# BitsyExpander_v3_0_M4.net
KiCad netlist of a schematic drawn in EAGLE
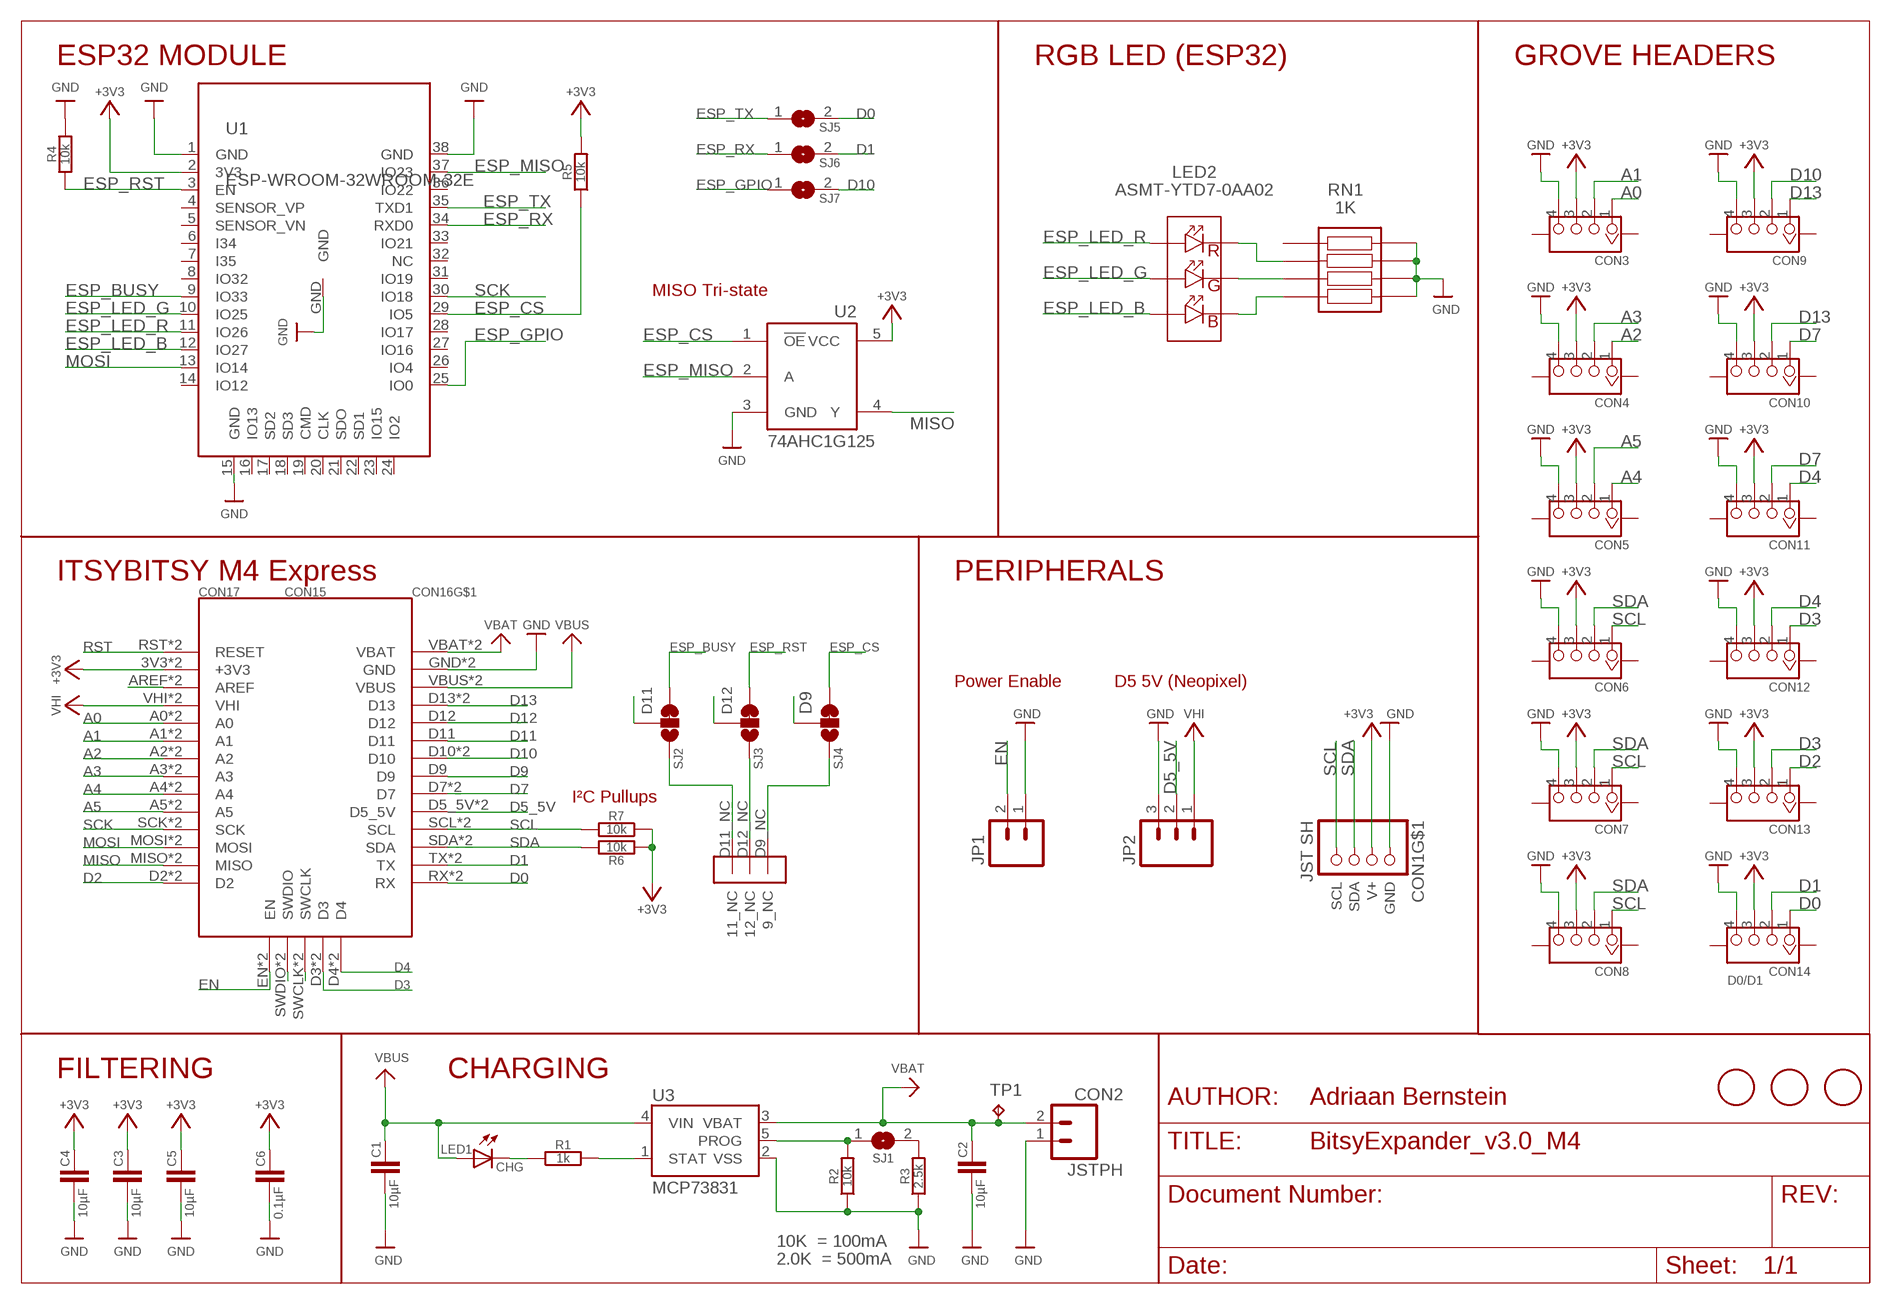
[diagram p0: schematic, sheet 1]

(export (version "E")
  (design (tool "Eeschema 10.0.6"))
  (components
    (comp (ref "C1")
      (value "10µF")
      (footprint "eagle-import:C0805")
      (libsource (lib "eagle-import") (part "C-EUC0805"))
    )
    (comp (ref "C2")
      (value "10µF")
      (footprint "eagle-import:C0805")
      (libsource (lib "eagle-import") (part "C-EUC0805"))
    )
    (comp (ref "C3")
      (value "10µF")
      (footprint "eagle-import:C0805")
      (libsource (lib "eagle-import") (part "C-EUC0805"))
    )
    (comp (ref "C4")
      (value "10µF")
      (footprint "eagle-import:C0805")
      (libsource (lib "eagle-import") (part "C-EUC0805"))
    )
    (comp (ref "C5")
      (value "10µF")
      (footprint "eagle-import:C0805")
      (libsource (lib "eagle-import") (part "C-EUC0805"))
    )
    (comp (ref "C6")
      (value "0.1µF")
      (footprint "eagle-import:C0805")
      (libsource (lib "eagle-import") (part "C-EUC0805"))
    )
    (comp (ref "CON1")
      (value "JST SH")
      (footprint "eagle-import:JST_SH4")
      (libsource (lib "eagle-import") (part "STEMMA_I2C_QT"))
    )
    (comp (ref "CON2")
      (value "JSTPH")
      (footprint "eagle-import:JST-2-SMD")
      (libsource (lib "eagle-import") (part "M02-JST-2MM-SMT"))
    )
    (comp (ref "CON3")
      (value "H4P-SMD-2.0")
      (footprint "eagle-import:HW4-PTH-2.0")
      (libsource (lib "eagle-import") (part "GROVE-CONNECTOR-4PINHW4-PTH-2.0"))
    )
    (comp (ref "CON4")
      (value "H4P-SMD-2.0")
      (footprint "eagle-import:HW4-PTH-2.0")
      (libsource (lib "eagle-import") (part "GROVE-CONNECTOR-4PINHW4-PTH-2.0"))
    )
    (comp (ref "CON5")
      (value "H4P-SMD-2.0")
      (footprint "eagle-import:HW4-PTH-2.0")
      (libsource (lib "eagle-import") (part "GROVE-CONNECTOR-4PINHW4-PTH-2.0"))
    )
    (comp (ref "CON6")
      (value "H4P-SMD-2.0")
      (footprint "eagle-import:HW4-PTH-2.0")
      (libsource (lib "eagle-import") (part "GROVE-CONNECTOR-4PINHW4-PTH-2.0"))
    )
    (comp (ref "CON7")
      (value "H4P-SMD-2.0")
      (footprint "eagle-import:HW4-PTH-2.0")
      (libsource (lib "eagle-import") (part "GROVE-CONNECTOR-4PINHW4-PTH-2.0"))
    )
    (comp (ref "CON8")
      (value "H4P-SMD-2.0")
      (footprint "eagle-import:HW4-PTH-2.0")
      (libsource (lib "eagle-import") (part "GROVE-CONNECTOR-4PINHW4-PTH-2.0"))
    )
    (comp (ref "CON9")
      (value "H4P-SMD-2.0")
      (footprint "eagle-import:HW4-PTH-2.0")
      (libsource (lib "eagle-import") (part "GROVE-CONNECTOR-4PINHW4-PTH-2.0"))
    )
    (comp (ref "CON10")
      (value "H4P-SMD-2.0")
      (footprint "eagle-import:HW4-PTH-2.0")
      (libsource (lib "eagle-import") (part "GROVE-CONNECTOR-4PINHW4-PTH-2.0"))
    )
    (comp (ref "CON11")
      (value "H4P-SMD-2.0")
      (footprint "eagle-import:HW4-PTH-2.0")
      (libsource (lib "eagle-import") (part "GROVE-CONNECTOR-4PINHW4-PTH-2.0"))
    )
    (comp (ref "CON12")
      (value "H4P-SMD-2.0")
      (footprint "eagle-import:HW4-PTH-2.0")
      (libsource (lib "eagle-import") (part "GROVE-CONNECTOR-4PINHW4-PTH-2.0"))
    )
    (comp (ref "CON13")
      (value "H4P-SMD-2.0")
      (footprint "eagle-import:HW4-PTH-2.0")
      (libsource (lib "eagle-import") (part "GROVE-CONNECTOR-4PINHW4-PTH-2.0"))
    )
    (comp (ref "CON14")
      (value "H4P-SMD-2.0")
      (footprint "eagle-import:HW4-PTH-2.0")
      (libsource (lib "eagle-import") (part "GROVE-CONNECTOR-4PINHW4-PTH-2.0"))
    )
    (comp (ref "CON15")
      (value "ITSYBITSY_EDGE_DEBUG")
      (footprint "eagle-import:ITSYBITSY_PTH_EDGE_DEBUG")
      (libsource (lib "eagle-import") (part "ITSYBITSY_EDGE_DEBUG"))
    )
    (comp (ref "CON16")
      (value "ITSYBITSY_EDGE_GND")
      (footprint "eagle-import:ITSYBITSY_SMD_EDGE_GND")
      (libsource (lib "eagle-import") (part "ITSYBITSY_EDGE_GND"))
    )
    (comp (ref "CON17")
      (value "ITSYBITSY_EDGE_PWR_M4EXPRESS")
      (footprint "eagle-import:ITSYBITSY_SMD_EDGE_PWR_M4EXPRESS")
      (libsource (lib "eagle-import") (part "ITSYBITSY_EDGE_PWR_M4EXPRESS"))
    )
    (comp (ref "FD1")
      (value "FIDUCIAL")
      (footprint "eagle-import:FIDUCIAL_1MM")
      (libsource (lib "eagle-import") (part "FIDUCIAL"))
    )
    (comp (ref "FD2")
      (value "FIDUCIAL")
      (footprint "eagle-import:FIDUCIAL_1MM")
      (libsource (lib "eagle-import") (part "FIDUCIAL"))
    )
    (comp (ref "FD3")
      (value "FIDUCIAL")
      (footprint "eagle-import:FIDUCIAL_1MM")
      (libsource (lib "eagle-import") (part "FIDUCIAL"))
    )
    (comp (ref "JP1")
      (value "M02PTH")
      (footprint "eagle-import:1X02")
      (libsource (lib "eagle-import") (part "M02PTH"))
    )
    (comp (ref "JP2")
      (value "M03PTH")
      (footprint "eagle-import:1X03")
      (libsource (lib "eagle-import") (part "M03PTH"))
    )
    (comp (ref "LED1")
      (value "CHG")
      (footprint "eagle-import:CHIP-LED0603")
      (libsource (lib "eagle-import") (part "LEDCHIP-LED0603"))
    )
    (comp (ref "LED2")
      (value "ASMT-YTD7-0AA02")
      (footprint "eagle-import:ASMTYTD70AA02")
      (fields (field (name "MOUSER_PART_NUMBER") "630-ASMT-YTD7-0AA02"))
      (libsource (lib "eagle-import") (part "ASMT-YTD7-0AA02"))
    )
    (comp (ref "R1")
      (value "1k")
      (footprint "eagle-import:R0603")
      (libsource (lib "eagle-import") (part "R-EU_R0603"))
    )
    (comp (ref "R2")
      (value "10k")
      (footprint "eagle-import:R0603")
      (libsource (lib "eagle-import") (part "R-EU_R0603"))
    )
    (comp (ref "R3")
      (value "2.5k")
      (footprint "eagle-import:R0603")
      (libsource (lib "eagle-import") (part "R-EU_R0603"))
    )
    (comp (ref "R4")
      (value "10k")
      (footprint "eagle-import:R0603")
      (libsource (lib "eagle-import") (part "R-EU_R0603"))
    )
    (comp (ref "R5")
      (value "10k")
      (footprint "eagle-import:R0603")
      (libsource (lib "eagle-import") (part "R-EU_R0603"))
    )
    (comp (ref "R6")
      (value "10k")
      (footprint "eagle-import:R0603")
      (libsource (lib "eagle-import") (part "R-EU_R0603"))
    )
    (comp (ref "R7")
      (value "10k")
      (footprint "eagle-import:R0603")
      (libsource (lib "eagle-import") (part "R-EU_R0603"))
    )
    (comp (ref "RN1")
      (value "1K")
      (footprint "eagle-import:CAY1647R0F4LF")
      (fields
        (field (name "MANUFACTURER_PART_NUMBER") "CAY16-221J4AS")
        (field (name "MOUSER_PART_NUMBER") "652-CAY16-221J4AS")
      )
      (libsource (lib "eagle-import") (part "CAY16-221J4AS"))
    )
    (comp (ref "SJ1") (value "SJ") (footprint "eagle-import:SJ") (libsource (lib "eagle-import") (part "SJ")))
    (comp (ref "SJ5") (value "SJ") (footprint "eagle-import:SJ") (libsource (lib "eagle-import") (part "SJ")))
    (comp (ref "SJ6") (value "SJ") (footprint "eagle-import:SJ") (libsource (lib "eagle-import") (part "SJ")))
    (comp (ref "SJ7") (value "SJ") (footprint "eagle-import:SJ") (libsource (lib "eagle-import") (part "SJ")))
    (comp (ref "SJ_D11")
      (value "SJ2")
      (footprint "eagle-import:SJ_2WAY_CLOSED")
      (libsource (lib "eagle-import") (part "SJ_2WAY_CLOSED"))
    )
    (comp (ref "SJ_D12")
      (value "SJ3")
      (footprint "eagle-import:SJ_2WAY_CLOSED")
      (libsource (lib "eagle-import") (part "SJ_2WAY_CLOSED"))
    )
    (comp (ref "SJ_D13")
      (value "SJ4")
      (footprint "eagle-import:SJ_2WAY_CLOSED")
      (libsource (lib "eagle-import") (part "SJ_2WAY_CLOSED"))
    )
    (comp (ref "TP1")
      (value "TPB1,27")
      (footprint "eagle-import:B1,27")
      (libsource (lib "eagle-import") (part "TPB1,27"))
    )
    (comp (ref "U1")
      (value "ESP-WROOM-32WROOM-32E")
      (footprint "eagle-import:ESP-WROOM-32E")
      (libsource (lib "eagle-import") (part "ESP-WROOM-32WROOM-32E"))
    )
    (comp (ref "U2")
      (value "74AHC1G125")
      (footprint "eagle-import:SOT23-5L")
      (libsource (lib "eagle-import") (part "74AHC1G125"))
    )
    (comp (ref "U3")
      (value "MCP73831")
      (footprint "eagle-import:SOT23-5")
      (libsource (lib "eagle-import") (part "MCP73831"))
    )
  )
  (nets
    (net (code "1") (name "+3V3") (class "Default")
      (node (ref "C3") (pin "1") (pinfunction "1_1") (pintype "passive"))
      (node (ref "C4") (pin "1") (pinfunction "1_1") (pintype "passive"))
      (node (ref "C5") (pin "1") (pinfunction "1_1") (pintype "passive"))
      (node (ref "C6") (pin "1") (pinfunction "1_1") (pintype "passive"))
      (node (ref "CON1") (pin "2") (pinfunction "V+_2") (pintype "passive"))
      (node (ref "CON10") (pin "3") (pinfunction "3_3") (pintype "bidirectional"))
      (node (ref "CON11") (pin "3") (pinfunction "3_3") (pintype "bidirectional"))
      (node (ref "CON12") (pin "3") (pinfunction "3_3") (pintype "bidirectional"))
      (node (ref "CON13") (pin "3") (pinfunction "3_3") (pintype "bidirectional"))
      (node (ref "CON14") (pin "3") (pinfunction "3_3") (pintype "bidirectional"))
      (node (ref "CON17") (pin "3V3") (pinfunction "+3V3_3V3") (pintype "bidirectional"))
      (node (ref "CON17") (pin "3V3_2") (pinfunction "+3V3_3V3_2") (pintype "bidirectional"))
      (node (ref "CON3") (pin "3") (pinfunction "3_3") (pintype "bidirectional"))
      (node (ref "CON4") (pin "3") (pinfunction "3_3") (pintype "bidirectional"))
      (node (ref "CON5") (pin "3") (pinfunction "3_3") (pintype "bidirectional"))
      (node (ref "CON6") (pin "3") (pinfunction "3_3") (pintype "bidirectional"))
      (node (ref "CON7") (pin "3") (pinfunction "3_3") (pintype "bidirectional"))
      (node (ref "CON8") (pin "3") (pinfunction "3_3") (pintype "bidirectional"))
      (node (ref "CON9") (pin "3") (pinfunction "3_3") (pintype "bidirectional"))
      (node (ref "R5") (pin "2") (pinfunction "2_2") (pintype "passive"))
      (node (ref "R6") (pin "1") (pinfunction "1_1") (pintype "passive"))
      (node (ref "R7") (pin "1") (pinfunction "1_1") (pintype "passive"))
      (node (ref "U1") (pin "2") (pinfunction "3V3_2") (pintype "bidirectional"))
      (node (ref "U2") (pin "5") (pinfunction "VCC_5") (pintype "power_in"))
    )
    (net (code "2") (name "/A0") (class "Default")
      (node (ref "CON17") (pin "A0") (pinfunction "A0_A0") (pintype "bidirectional"))
      (node (ref "CON17") (pin "A0_2") (pinfunction "A0_A0_2") (pintype "bidirectional"))
      (node (ref "CON3") (pin "1") (pinfunction "1_1") (pintype "bidirectional"))
    )
    (net (code "3") (name "/A1") (class "Default")
      (node (ref "CON17") (pin "A1") (pinfunction "A1_A1") (pintype "bidirectional"))
      (node (ref "CON17") (pin "A1_2") (pinfunction "A1_A1_2") (pintype "bidirectional"))
      (node (ref "CON3") (pin "2") (pinfunction "2_2") (pintype "bidirectional"))
    )
    (net (code "4") (name "/A2") (class "Default")
      (node (ref "CON17") (pin "A2") (pinfunction "A2_A2") (pintype "bidirectional"))
      (node (ref "CON17") (pin "A2_2") (pinfunction "A2_A2_2") (pintype "bidirectional"))
      (node (ref "CON4") (pin "1") (pinfunction "1_1") (pintype "bidirectional"))
    )
    (net (code "5") (name "/A3") (class "Default")
      (node (ref "CON17") (pin "A3") (pinfunction "A3_A3") (pintype "bidirectional"))
      (node (ref "CON17") (pin "A3_2") (pinfunction "A3_A3_2") (pintype "bidirectional"))
      (node (ref "CON4") (pin "2") (pinfunction "2_2") (pintype "bidirectional"))
    )
    (net (code "6") (name "/A4") (class "Default")
      (node (ref "CON17") (pin "A4") (pinfunction "A4_A4") (pintype "bidirectional"))
      (node (ref "CON17") (pin "A4_2") (pinfunction "A4_A4_2") (pintype "bidirectional"))
      (node (ref "CON5") (pin "1") (pinfunction "1_1") (pintype "bidirectional"))
    )
    (net (code "7") (name "/A5") (class "Default")
      (node (ref "CON17") (pin "A5") (pinfunction "A5_A5") (pintype "bidirectional"))
      (node (ref "CON17") (pin "A5_2") (pinfunction "A5_A5_2") (pintype "bidirectional"))
      (node (ref "CON5") (pin "2") (pinfunction "2_2") (pintype "bidirectional"))
    )
    (net (code "8") (name "/D0") (class "Default")
      (node (ref "CON14") (pin "1") (pinfunction "1_1") (pintype "bidirectional"))
      (node (ref "CON15") (pin "RX") (pinfunction "RX_RX") (pintype "bidirectional"))
      (node (ref "CON15") (pin "RX_2") (pinfunction "RX_RX_2") (pintype "bidirectional"))
      (node (ref "SJ5") (pin "2") (pinfunction "2_2") (pintype "passive"))
    )
    (net (code "9") (name "/D1") (class "Default")
      (node (ref "CON14") (pin "2") (pinfunction "2_2") (pintype "bidirectional"))
      (node (ref "CON16") (pin "TX") (pinfunction "TX_TX") (pintype "bidirectional"))
      (node (ref "CON16") (pin "TX_2") (pinfunction "TX_TX_2") (pintype "bidirectional"))
      (node (ref "SJ6") (pin "2") (pinfunction "2_2") (pintype "passive"))
    )
    (net (code "10") (name "/D2") (class "Default")
      (node (ref "CON13") (pin "1") (pinfunction "1_1") (pintype "bidirectional"))
      (node (ref "CON15") (pin "D2") (pinfunction "D2_D2") (pintype "bidirectional"))
      (node (ref "CON15") (pin "D2_2") (pinfunction "D2_D2_2") (pintype "bidirectional"))
    )
    (net (code "11") (name "/D3") (class "Default")
      (node (ref "CON12") (pin "1") (pinfunction "1_1") (pintype "bidirectional"))
      (node (ref "CON13") (pin "2") (pinfunction "2_2") (pintype "bidirectional"))
      (node (ref "CON15") (pin "D3") (pinfunction "D3_D3") (pintype "bidirectional"))
      (node (ref "CON15") (pin "D3_2") (pinfunction "D3_D3_2") (pintype "bidirectional"))
    )
    (net (code "12") (name "/D4") (class "Default")
      (node (ref "CON11") (pin "1") (pinfunction "1_1") (pintype "bidirectional"))
      (node (ref "CON12") (pin "2") (pinfunction "2_2") (pintype "bidirectional"))
      (node (ref "CON15") (pin "D4") (pinfunction "D4_D4") (pintype "bidirectional"))
      (node (ref "CON15") (pin "D4_2") (pinfunction "D4_D4_2") (pintype "bidirectional"))
    )
    (net (code "13") (name "/D5_5V") (class "Default")
      (node (ref "CON16") (pin "D5_5V") (pinfunction "D5_5V_D5_5V") (pintype "bidirectional"))
      (node (ref "CON16") (pin "D5_5V_2") (pinfunction "D5_5V_D5_5V_2") (pintype "bidirectional"))
      (node (ref "JP2") (pin "2") (pinfunction "2_2") (pintype "passive"))
    )
    (net (code "14") (name "/D7") (class "Default")
      (node (ref "CON10") (pin "1") (pinfunction "1_1") (pintype "bidirectional"))
      (node (ref "CON11") (pin "2") (pinfunction "2_2") (pintype "bidirectional"))
      (node (ref "CON16") (pin "D7") (pinfunction "D7_D7") (pintype "bidirectional"))
      (node (ref "CON16") (pin "D7_2") (pinfunction "D7_D7_2") (pintype "bidirectional"))
    )
    (net (code "15") (name "/D9") (class "Default")
      (node (ref "CON16") (pin "D9") (pinfunction "D9_D9") (pintype "bidirectional"))
      (node (ref "SJ_D13") (pin "2") (pinfunction "2_2") (pintype "passive"))
    )
    (net (code "16") (name "/D10") (class "Default")
      (node (ref "CON16") (pin "D10") (pinfunction "D10_D10") (pintype "bidirectional"))
      (node (ref "CON16") (pin "D10_2") (pinfunction "D10_D10_2") (pintype "bidirectional"))
      (node (ref "CON9") (pin "2") (pinfunction "2_2") (pintype "bidirectional"))
      (node (ref "SJ7") (pin "2") (pinfunction "2_2") (pintype "passive"))
    )
    (net (code "17") (name "/D11") (class "Default")
      (node (ref "CON16") (pin "D11") (pinfunction "D11_D11") (pintype "bidirectional"))
      (node (ref "SJ_D11") (pin "2") (pinfunction "2_2") (pintype "passive"))
    )
    (net (code "18") (name "/D12") (class "Default")
      (node (ref "CON16") (pin "D12") (pinfunction "D12_D12") (pintype "bidirectional"))
      (node (ref "SJ_D12") (pin "2") (pinfunction "2_2") (pintype "passive"))
    )
    (net (code "19") (name "/D13") (class "Default")
      (node (ref "CON10") (pin "2") (pinfunction "2_2") (pintype "bidirectional"))
      (node (ref "CON16") (pin "D13") (pinfunction "D13_D13") (pintype "bidirectional"))
      (node (ref "CON16") (pin "D13_2") (pinfunction "D13_D13_2") (pintype "bidirectional"))
      (node (ref "CON9") (pin "1") (pinfunction "1_1") (pintype "bidirectional"))
    )
    (net (code "20") (name "/EN") (class "Default")
      (node (ref "CON15") (pin "EN") (pinfunction "EN_EN") (pintype "bidirectional"))
      (node (ref "CON15") (pin "EN_2") (pinfunction "EN_EN_2") (pintype "bidirectional"))
      (node (ref "JP1") (pin "2") (pinfunction "2_2") (pintype "passive"))
    )
    (net (code "21") (name "/ESP_BUSY") (class "Default")
      (node (ref "SJ_D11") (pin "1") (pinfunction "1_1") (pintype "passive"))
      (node (ref "U1") (pin "9") (pinfunction "IO33_9") (pintype "bidirectional"))
    )
    (net (code "22") (name "/ESP_CS") (class "Default")
      (node (ref "R5") (pin "1") (pinfunction "1_1") (pintype "passive"))
      (node (ref "SJ_D13") (pin "1") (pinfunction "1_1") (pintype "passive"))
      (node (ref "U1") (pin "29") (pinfunction "IO5_29") (pintype "bidirectional"))
      (node (ref "U2") (pin "1") (pinfunction "~{OE}_1") (pintype "input"))
    )
    (net (code "23") (name "/ESP_GPIO") (class "Default")
      (node (ref "SJ7") (pin "1") (pinfunction "1_1") (pintype "passive"))
      (node (ref "U1") (pin "25") (pinfunction "IO0_25") (pintype "bidirectional"))
    )
    (net (code "24") (name "/ESP_LED_B") (class "Default")
      (node (ref "LED2") (pin "6") (pinfunction "A_BLUE_6") (pintype "bidirectional"))
      (node (ref "U1") (pin "12") (pinfunction "IO27_12") (pintype "bidirectional"))
    )
    (net (code "25") (name "/ESP_LED_G") (class "Default")
      (node (ref "LED2") (pin "5") (pinfunction "A_GREEN_5") (pintype "bidirectional"))
      (node (ref "U1") (pin "10") (pinfunction "IO25_10") (pintype "bidirectional"))
    )
    (net (code "26") (name "/ESP_LED_R") (class "Default")
      (node (ref "LED2") (pin "4") (pinfunction "A_RED_4") (pintype "bidirectional"))
      (node (ref "U1") (pin "11") (pinfunction "IO26_11") (pintype "bidirectional"))
    )
    (net (code "27") (name "/ESP_MISO") (class "Default")
      (node (ref "U1") (pin "37") (pinfunction "IO23_37") (pintype "bidirectional"))
      (node (ref "U2") (pin "2") (pinfunction "A_2") (pintype "input"))
    )
    (net (code "28") (name "/ESP_RST") (class "Default")
      (node (ref "R4") (pin "1") (pinfunction "1_1") (pintype "passive"))
      (node (ref "SJ_D12") (pin "1") (pinfunction "1_1") (pintype "passive"))
      (node (ref "U1") (pin "3") (pinfunction "EN_3") (pintype "bidirectional"))
    )
    (net (code "29") (name "/ESP_RX") (class "Default")
      (node (ref "SJ6") (pin "1") (pinfunction "1_1") (pintype "passive"))
      (node (ref "U1") (pin "34") (pinfunction "RXD0_34") (pintype "bidirectional"))
    )
    (net (code "30") (name "/ESP_TX") (class "Default")
      (node (ref "SJ5") (pin "1") (pinfunction "1_1") (pintype "passive"))
      (node (ref "U1") (pin "35") (pinfunction "TXD1_35") (pintype "bidirectional"))
    )
    (net (code "31") (name "/MISO") (class "Default")
      (node (ref "CON17") (pin "MISO") (pinfunction "MISO_MISO") (pintype "bidirectional"))
      (node (ref "CON17") (pin "MISO_2") (pinfunction "MISO_MISO_2") (pintype "bidirectional"))
      (node (ref "U2") (pin "4") (pinfunction "Y_4") (pintype "output"))
    )
    (net (code "32") (name "/MOSI") (class "Default")
      (node (ref "CON17") (pin "MOSI") (pinfunction "MOSI_MOSI") (pintype "bidirectional"))
      (node (ref "CON17") (pin "MOSI_2") (pinfunction "MOSI_MOSI_2") (pintype "bidirectional"))
      (node (ref "U1") (pin "13") (pinfunction "IO14_13") (pintype "bidirectional"))
    )
    (net (code "33") (name "/RST") (class "Default")
      (node (ref "CON17") (pin "RST") (pinfunction "RESET_RST") (pintype "bidirectional"))
      (node (ref "CON17") (pin "RST_2") (pinfunction "RESET_RST_2") (pintype "bidirectional"))
    )
    (net (code "34") (name "/SCK") (class "Default")
      (node (ref "CON17") (pin "SCK") (pinfunction "SCK_SCK") (pintype "bidirectional"))
      (node (ref "CON17") (pin "SCK_2") (pinfunction "SCK_SCK_2") (pintype "bidirectional"))
      (node (ref "U1") (pin "30") (pinfunction "IO18_30") (pintype "bidirectional"))
    )
    (net (code "35") (name "/SCL") (class "Default")
      (node (ref "CON1") (pin "4") (pinfunction "SCL_4") (pintype "passive"))
      (node (ref "CON16") (pin "SCL") (pinfunction "SCL_SCL") (pintype "bidirectional"))
      (node (ref "CON16") (pin "SCL_2") (pinfunction "SCL_SCL_2") (pintype "bidirectional"))
      (node (ref "CON6") (pin "1") (pinfunction "1_1") (pintype "bidirectional"))
      (node (ref "CON7") (pin "1") (pinfunction "1_1") (pintype "bidirectional"))
      (node (ref "CON8") (pin "1") (pinfunction "1_1") (pintype "bidirectional"))
      (node (ref "R7") (pin "2") (pinfunction "2_2") (pintype "passive"))
    )
    (net (code "36") (name "/SDA") (class "Default")
      (node (ref "CON1") (pin "3") (pinfunction "SDA_3") (pintype "passive"))
      (node (ref "CON16") (pin "SDA") (pinfunction "SDA_SDA") (pintype "bidirectional"))
      (node (ref "CON16") (pin "SDA_2") (pinfunction "SDA_SDA_2") (pintype "bidirectional"))
      (node (ref "CON6") (pin "2") (pinfunction "2_2") (pintype "bidirectional"))
      (node (ref "CON7") (pin "2") (pinfunction "2_2") (pintype "bidirectional"))
      (node (ref "CON8") (pin "2") (pinfunction "2_2") (pintype "bidirectional"))
      (node (ref "R6") (pin "2") (pinfunction "2_2") (pintype "passive"))
    )
    (net (code "37") (name "GND") (class "Default")
      (node (ref "C1") (pin "2") (pinfunction "2_2") (pintype "passive"))
      (node (ref "C2") (pin "2") (pinfunction "2_2") (pintype "passive"))
      (node (ref "C3") (pin "2") (pinfunction "2_2") (pintype "passive"))
      (node (ref "C4") (pin "2") (pinfunction "2_2") (pintype "passive"))
      (node (ref "C5") (pin "2") (pinfunction "2_2") (pintype "passive"))
      (node (ref "C6") (pin "2") (pinfunction "2_2") (pintype "passive"))
      (node (ref "CON1") (pin "1") (pinfunction "GND_1") (pintype "passive"))
      (node (ref "CON10") (pin "4") (pinfunction "4_4") (pintype "bidirectional"))
      (node (ref "CON11") (pin "4") (pinfunction "4_4") (pintype "bidirectional"))
      (node (ref "CON12") (pin "4") (pinfunction "4_4") (pintype "bidirectional"))
      (node (ref "CON13") (pin "4") (pinfunction "4_4") (pintype "bidirectional"))
      (node (ref "CON14") (pin "4") (pinfunction "4_4") (pintype "bidirectional"))
      (node (ref "CON16") (pin "GND") (pinfunction "GND_GND") (pintype "bidirectional"))
      (node (ref "CON16") (pin "GND_2") (pinfunction "GND_GND_2") (pintype "bidirectional"))
      (node (ref "CON2") (pin "1") (pinfunction "1_1") (pintype "passive"))
      (node (ref "CON3") (pin "4") (pinfunction "4_4") (pintype "bidirectional"))
      (node (ref "CON4") (pin "4") (pinfunction "4_4") (pintype "bidirectional"))
      (node (ref "CON5") (pin "4") (pinfunction "4_4") (pintype "bidirectional"))
      (node (ref "CON6") (pin "4") (pinfunction "4_4") (pintype "bidirectional"))
      (node (ref "CON7") (pin "4") (pinfunction "4_4") (pintype "bidirectional"))
      (node (ref "CON8") (pin "4") (pinfunction "4_4") (pintype "bidirectional"))
      (node (ref "CON9") (pin "4") (pinfunction "4_4") (pintype "bidirectional"))
      (node (ref "JP1") (pin "1") (pinfunction "1_1") (pintype "passive"))
      (node (ref "JP2") (pin "3") (pinfunction "3_3") (pintype "passive"))
      (node (ref "R2") (pin "1") (pinfunction "1_1") (pintype "passive"))
      (node (ref "R3") (pin "1") (pinfunction "1_1") (pintype "passive"))
      (node (ref "R4") (pin "2") (pinfunction "2_2") (pintype "passive"))
      (node (ref "RN1") (pin "5") (pinfunction "R4_2_5") (pintype "bidirectional"))
      (node (ref "RN1") (pin "6") (pinfunction "R3_2_6") (pintype "bidirectional"))
      (node (ref "RN1") (pin "7") (pinfunction "R2_2_7") (pintype "bidirectional"))
      (node (ref "RN1") (pin "8") (pinfunction "R1_2_8") (pintype "bidirectional"))
      (node (ref "U1") (pin "1") (pinfunction "GND_1") (pintype "bidirectional"))
      (node (ref "U1") (pin "15") (pinfunction "GND_15") (pintype "bidirectional"))
      (node (ref "U1") (pin "38") (pinfunction "GND_38") (pintype "bidirectional"))
      (node (ref "U1") (pin "GND") (pinfunction "GND_GND") (pintype "bidirectional"))
      (node (ref "U2") (pin "3") (pinfunction "GND_3") (pintype "power_in"))
      (node (ref "U3") (pin "2") (pinfunction "VSS_2") (pintype "power_in"))
    )
    (net (code "38") (name "Net-(CON15-PadSWCLK)") (class "Default")
      (node (ref "CON15") (pin "SWCLK") (pinfunction "SWCLK_SWCLK") (pintype "bidirectional"))
      (node (ref "CON15") (pin "SWCLK_2") (pinfunction "SWCLK_SWCLK_2") (pintype "bidirectional"))
    )
    (net (code "39") (name "Net-(CON15-PadSWDIO)") (class "Default")
      (node (ref "CON15") (pin "SWDIO") (pinfunction "SWDIO_SWDIO") (pintype "bidirectional"))
      (node (ref "CON15") (pin "SWDIO_2") (pinfunction "SWDIO_SWDIO_2") (pintype "bidirectional"))
    )
    (net (code "40") (name "Net-(CON16B-9_NC)") (class "Default")
      (node (ref "CON16") (pin "D9_NC") (pinfunction "9_NC_D9_NC") (pintype "bidirectional"))
      (node (ref "SJ_D13") (pin "3") (pinfunction "3_3") (pintype "passive"))
    )
    (net (code "41") (name "Net-(CON16B-11_NC)") (class "Default")
      (node (ref "CON16") (pin "D11_NC") (pinfunction "11_NC_D11_NC") (pintype "bidirectional"))
      (node (ref "SJ_D11") (pin "3") (pinfunction "3_3") (pintype "passive"))
    )
    (net (code "42") (name "Net-(CON16B-12_NC)") (class "Default")
      (node (ref "CON16") (pin "D12_NC") (pinfunction "12_NC_D12_NC") (pintype "bidirectional"))
      (node (ref "SJ_D12") (pin "3") (pinfunction "3_3") (pintype "passive"))
    )
    (net (code "43") (name "Net-(CON17-AREF-PadAREF_2)") (class "Default")
      (node (ref "CON17") (pin "AREF") (pinfunction "AREF_AREF") (pintype "bidirectional"))
      (node (ref "CON17") (pin "AREF_2") (pinfunction "AREF_AREF_2") (pintype "bidirectional"))
    )
    (net (code "44") (name "Net-(LED1-PadC)") (class "Default")
      (node (ref "LED1") (pin "C") (pinfunction "C_C") (pintype "passive"))
      (node (ref "R1") (pin "1") (pinfunction "1_1") (pintype "passive"))
    )
    (net (code "45") (name "Net-(LED2-K_BLUE)") (class "Default")
      (node (ref "LED2") (pin "1") (pinfunction "K_BLUE_1") (pintype "bidirectional"))
      (node (ref "RN1") (pin "4") (pinfunction "R4_1_4") (pintype "bidirectional"))
    )
    (net (code "46") (name "Net-(LED2-K_GREEN)") (class "Default")
      (node (ref "LED2") (pin "2") (pinfunction "K_GREEN_2") (pintype "bidirectional"))
      (node (ref "RN1") (pin "3") (pinfunction "R3_1_3") (pintype "bidirectional"))
    )
    (net (code "47") (name "Net-(LED2-K_RED)") (class "Default")
      (node (ref "LED2") (pin "3") (pinfunction "K_RED_3") (pintype "bidirectional"))
      (node (ref "RN1") (pin "2") (pinfunction "R2_1_2") (pintype "bidirectional"))
    )
    (net (code "48") (name "Net-(R3-Pad2)") (class "Default")
      (node (ref "R3") (pin "2") (pinfunction "2_2") (pintype "passive"))
      (node (ref "SJ1") (pin "2") (pinfunction "2_2") (pintype "passive"))
    )
    (net (code "49") (name "Net-(U3-PROG)") (class "Default")
      (node (ref "R2") (pin "2") (pinfunction "2_2") (pintype "passive"))
      (node (ref "SJ1") (pin "1") (pinfunction "1_1") (pintype "passive"))
      (node (ref "U3") (pin "5") (pinfunction "PROG_5") (pintype "input"))
    )
    (net (code "50") (name "Net-(U3-STAT)") (class "Default")
      (node (ref "R1") (pin "2") (pinfunction "2_2") (pintype "passive"))
      (node (ref "U3") (pin "1") (pinfunction "STAT_1") (pintype "output"))
    )
    (net (code "51") (name "VBAT") (class "Default")
      (node (ref "C2") (pin "1") (pinfunction "1_1") (pintype "passive"))
      (node (ref "CON16") (pin "VBAT") (pinfunction "VBAT_VBAT") (pintype "bidirectional"))
      (node (ref "CON16") (pin "VBAT_2") (pinfunction "VBAT_VBAT_2") (pintype "bidirectional"))
      (node (ref "CON2") (pin "2") (pinfunction "2_2") (pintype "passive"))
      (node (ref "TP1") (pin "TP") (pinfunction "TP_TP") (pintype "input"))
      (node (ref "U3") (pin "3") (pinfunction "VBAT_3") (pintype "power_in"))
    )
    (net (code "52") (name "VBUS") (class "Default")
      (node (ref "C1") (pin "1") (pinfunction "1_1") (pintype "passive"))
      (node (ref "CON16") (pin "VBUS") (pinfunction "VBUS_VBUS") (pintype "bidirectional"))
      (node (ref "CON16") (pin "VBUS_2") (pinfunction "VBUS_VBUS_2") (pintype "bidirectional"))
      (node (ref "LED1") (pin "A") (pinfunction "A_A") (pintype "passive"))
      (node (ref "U3") (pin "4") (pinfunction "VIN_4") (pintype "power_in"))
    )
    (net (code "53") (name "VHI") (class "Default")
      (node (ref "CON17") (pin "VHI") (pinfunction "VHI_VHI") (pintype "bidirectional"))
      (node (ref "CON17") (pin "VHI_2") (pinfunction "VHI_VHI_2") (pintype "bidirectional"))
      (node (ref "JP2") (pin "1") (pinfunction "1_1") (pintype "passive"))
    )
    (net (code "54") (name "unconnected-(CON3-SS1-Pad5)") (class "Default")
      (node (ref "CON3") (pin "5") (pinfunction "SS1_5") (pintype "bidirectional"))
    )
    (net (code "55") (name "unconnected-(CON3-SS2-Pad6)") (class "Default")
      (node (ref "CON3") (pin "6") (pinfunction "SS2_6") (pintype "bidirectional"))
    )
    (net (code "56") (name "unconnected-(CON4-SS1-Pad5)") (class "Default")
      (node (ref "CON4") (pin "5") (pinfunction "SS1_5") (pintype "bidirectional"))
    )
    (net (code "57") (name "unconnected-(CON4-SS2-Pad6)") (class "Default")
      (node (ref "CON4") (pin "6") (pinfunction "SS2_6") (pintype "bidirectional"))
    )
    (net (code "58") (name "unconnected-(CON5-SS1-Pad5)") (class "Default")
      (node (ref "CON5") (pin "5") (pinfunction "SS1_5") (pintype "bidirectional"))
    )
    (net (code "59") (name "unconnected-(CON5-SS2-Pad6)") (class "Default")
      (node (ref "CON5") (pin "6") (pinfunction "SS2_6") (pintype "bidirectional"))
    )
    (net (code "60") (name "unconnected-(CON6-SS1-Pad5)") (class "Default")
      (node (ref "CON6") (pin "5") (pinfunction "SS1_5") (pintype "bidirectional"))
    )
    (net (code "61") (name "unconnected-(CON6-SS2-Pad6)") (class "Default")
      (node (ref "CON6") (pin "6") (pinfunction "SS2_6") (pintype "bidirectional"))
    )
    (net (code "62") (name "unconnected-(CON7-SS1-Pad5)") (class "Default")
      (node (ref "CON7") (pin "5") (pinfunction "SS1_5") (pintype "bidirectional"))
    )
    (net (code "63") (name "unconnected-(CON7-SS2-Pad6)") (class "Default")
      (node (ref "CON7") (pin "6") (pinfunction "SS2_6") (pintype "bidirectional"))
    )
    (net (code "64") (name "unconnected-(CON8-SS1-Pad5)") (class "Default")
      (node (ref "CON8") (pin "5") (pinfunction "SS1_5") (pintype "bidirectional"))
    )
    (net (code "65") (name "unconnected-(CON8-SS2-Pad6)") (class "Default")
      (node (ref "CON8") (pin "6") (pinfunction "SS2_6") (pintype "bidirectional"))
    )
    (net (code "66") (name "unconnected-(CON9-SS1-Pad5)") (class "Default")
      (node (ref "CON9") (pin "5") (pinfunction "SS1_5") (pintype "bidirectional"))
    )
    (net (code "67") (name "unconnected-(CON9-SS2-Pad6)") (class "Default")
      (node (ref "CON9") (pin "6") (pinfunction "SS2_6") (pintype "bidirectional"))
    )
    (net (code "68") (name "unconnected-(CON10-SS1-Pad5)") (class "Default")
      (node (ref "CON10") (pin "5") (pinfunction "SS1_5") (pintype "bidirectional"))
    )
    (net (code "69") (name "unconnected-(CON10-SS2-Pad6)") (class "Default")
      (node (ref "CON10") (pin "6") (pinfunction "SS2_6") (pintype "bidirectional"))
    )
    (net (code "70") (name "unconnected-(CON11-SS1-Pad5)") (class "Default")
      (node (ref "CON11") (pin "5") (pinfunction "SS1_5") (pintype "bidirectional"))
    )
    (net (code "71") (name "unconnected-(CON11-SS2-Pad6)") (class "Default")
      (node (ref "CON11") (pin "6") (pinfunction "SS2_6") (pintype "bidirectional"))
    )
    (net (code "72") (name "unconnected-(CON12-SS1-Pad5)") (class "Default")
      (node (ref "CON12") (pin "5") (pinfunction "SS1_5") (pintype "bidirectional"))
    )
    (net (code "73") (name "unconnected-(CON12-SS2-Pad6)") (class "Default")
      (node (ref "CON12") (pin "6") (pinfunction "SS2_6") (pintype "bidirectional"))
    )
    (net (code "74") (name "unconnected-(CON13-SS1-Pad5)") (class "Default")
      (node (ref "CON13") (pin "5") (pinfunction "SS1_5") (pintype "bidirectional"))
    )
    (net (code "75") (name "unconnected-(CON13-SS2-Pad6)") (class "Default")
      (node (ref "CON13") (pin "6") (pinfunction "SS2_6") (pintype "bidirectional"))
    )
    (net (code "76") (name "unconnected-(CON14-SS1-Pad5)") (class "Default")
      (node (ref "CON14") (pin "5") (pinfunction "SS1_5") (pintype "bidirectional"))
    )
    (net (code "77") (name "unconnected-(CON14-SS2-Pad6)") (class "Default")
      (node (ref "CON14") (pin "6") (pinfunction "SS2_6") (pintype "bidirectional"))
    )
    (net (code "78") (name "unconnected-(RN1-R1_1-Pad1)") (class "Default")
      (node (ref "RN1") (pin "1") (pinfunction "R1_1_1") (pintype "bidirectional"))
    )
    (net (code "79") (name "unconnected-(U1-CLK-Pad20)") (class "Default")
      (node (ref "U1") (pin "20") (pinfunction "CLK_20") (pintype "bidirectional"))
    )
    (net (code "80") (name "unconnected-(U1-CMD-Pad19)") (class "Default")
      (node (ref "U1") (pin "19") (pinfunction "CMD_19") (pintype "bidirectional"))
    )
    (net (code "81") (name "unconnected-(U1-I34-Pad6)") (class "Default")
      (node (ref "U1") (pin "6") (pinfunction "I34_6") (pintype "input"))
    )
    (net (code "82") (name "unconnected-(U1-I35-Pad7)") (class "Default")
      (node (ref "U1") (pin "7") (pinfunction "I35_7") (pintype "input"))
    )
    (net (code "83") (name "unconnected-(U1-IO2-Pad24)") (class "Default")
      (node (ref "U1") (pin "24") (pinfunction "IO2_24") (pintype "bidirectional"))
    )
    (net (code "84") (name "unconnected-(U1-IO4-Pad26)") (class "Default")
      (node (ref "U1") (pin "26") (pinfunction "IO4_26") (pintype "bidirectional"))
    )
    (net (code "85") (name "unconnected-(U1-IO12-Pad14)") (class "Default")
      (node (ref "U1") (pin "14") (pinfunction "IO12_14") (pintype "bidirectional"))
    )
    (net (code "86") (name "unconnected-(U1-IO13-Pad16)") (class "Default")
      (node (ref "U1") (pin "16") (pinfunction "IO13_16") (pintype "bidirectional"))
    )
    (net (code "87") (name "unconnected-(U1-IO15-Pad23)") (class "Default")
      (node (ref "U1") (pin "23") (pinfunction "IO15_23") (pintype "bidirectional"))
    )
    (net (code "88") (name "unconnected-(U1-IO16-Pad27)") (class "Default")
      (node (ref "U1") (pin "27") (pinfunction "IO16_27") (pintype "bidirectional"))
    )
    (net (code "89") (name "unconnected-(U1-IO17-Pad28)") (class "Default")
      (node (ref "U1") (pin "28") (pinfunction "IO17_28") (pintype "bidirectional"))
    )
    (net (code "90") (name "unconnected-(U1-IO19-Pad31)") (class "Default")
      (node (ref "U1") (pin "31") (pinfunction "IO19_31") (pintype "bidirectional"))
    )
    (net (code "91") (name "unconnected-(U1-IO21-Pad33)") (class "Default")
      (node (ref "U1") (pin "33") (pinfunction "IO21_33") (pintype "bidirectional"))
    )
    (net (code "92") (name "unconnected-(U1-IO22-Pad36)") (class "Default")
      (node (ref "U1") (pin "36") (pinfunction "IO22_36") (pintype "bidirectional"))
    )
    (net (code "93") (name "unconnected-(U1-IO32-Pad8)") (class "Default")
      (node (ref "U1") (pin "8") (pinfunction "IO32_8") (pintype "bidirectional"))
    )
    (net (code "94") (name "unconnected-(U1-NC-Pad32)") (class "Default")
      (node (ref "U1") (pin "32") (pinfunction "NC_32") (pintype "bidirectional"))
    )
    (net (code "95") (name "unconnected-(U1-SD1-Pad22)") (class "Default")
      (node (ref "U1") (pin "22") (pinfunction "SD1_22") (pintype "bidirectional"))
    )
    (net (code "96") (name "unconnected-(U1-SD2-Pad17)") (class "Default")
      (node (ref "U1") (pin "17") (pinfunction "SD2_17") (pintype "bidirectional"))
    )
    (net (code "97") (name "unconnected-(U1-SD3-Pad18)") (class "Default")
      (node (ref "U1") (pin "18") (pinfunction "SD3_18") (pintype "bidirectional"))
    )
    (net (code "98") (name "unconnected-(U1-SDO-Pad21)") (class "Default")
      (node (ref "U1") (pin "21") (pinfunction "SDO_21") (pintype "bidirectional"))
    )
    (net (code "99") (name "unconnected-(U1-SENSOR_VN-Pad5)") (class "Default")
      (node (ref "U1") (pin "5") (pinfunction "SENSOR_VN_5") (pintype "input"))
    )
    (net (code "100") (name "unconnected-(U1-SENSOR_VP-Pad4)") (class "Default")
      (node (ref "U1") (pin "4") (pinfunction "SENSOR_VP_4") (pintype "input"))
    )
  )
)
